# Pic-Kit.net
KiCad netlist of a schematic drawn in Altium Designer
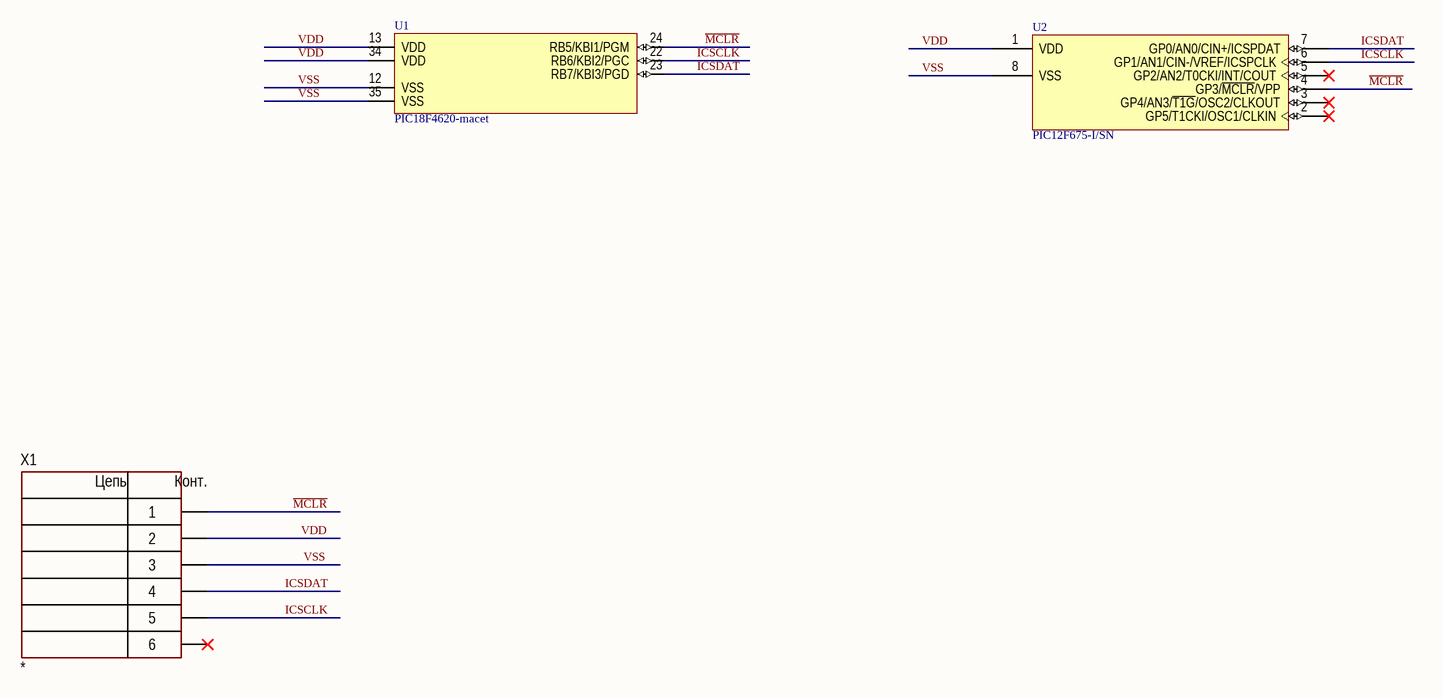
[diagram p0: Pic-Kit.SchDoc]

(export (version "E")
  (design (tool "Eeschema 10.0.6"))
  (components
    (comp (ref "U1")
      (value "PIC18F4620-macet")
      (footprint "PDIP600-P44")
      (description "44-Pin PDIP")
      (libsource (lib "Digital") (part "PIC18F4620-macet"))
    )
    (comp (ref "U2")
      (value "PIC12F675-I/SN")
      (footprint "PDIP300-P8")
      (description "FLASH-Based 8-Bit CMOS Microcontroller, 10-Bit A/D, 8-Pin SOIC 150mil, Industrial Temperature")
      (libsource (lib "Digital") (part "PIC12F675-I/SN"))
    )
    (comp (ref "X1") (value "*") (footprint "CON: PAD 6") (libsource (lib "Connectors") (part "6-Connector")))
  )
  (nets
    (net (code "1") (name "/ICSCLK") (class "Default")
      (node (ref "U1") (pin "22") (pinfunction "RB6/KBI2/PGC_22") (pintype "bidirectional"))
      (node (ref "U2") (pin "6") (pinfunction "GP1/AN1/CIN-/VREF/ICSPCLK_6") (pintype "bidirectional"))
      (node (ref "X1") (pin "5") (pinfunction "5_5") (pintype "power_in"))
    )
    (net (code "2") (name "/ICSDAT") (class "Default")
      (node (ref "U1") (pin "23") (pinfunction "RB7/KBI3/PGD_23") (pintype "bidirectional"))
      (node (ref "U2") (pin "7") (pinfunction "GP0/AN0/CIN+/ICSPDAT_7") (pintype "bidirectional"))
      (node (ref "X1") (pin "4") (pinfunction "4_4") (pintype "power_in"))
    )
    (net (code "3") (name "/VDD") (class "Default")
      (node (ref "U1") (pin "13") (pinfunction "VDD_13") (pintype "power_in"))
      (node (ref "U1") (pin "34") (pinfunction "VDD_34") (pintype "power_in"))
      (node (ref "U2") (pin "1") (pinfunction "VDD_1") (pintype "power_in"))
      (node (ref "X1") (pin "2") (pinfunction "2_2") (pintype "passive"))
    )
    (net (code "4") (name "/VSS") (class "Default")
      (node (ref "U1") (pin "12") (pinfunction "VSS_12") (pintype "power_in"))
      (node (ref "U1") (pin "35") (pinfunction "VSS_35") (pintype "power_in"))
      (node (ref "U2") (pin "8") (pinfunction "VSS_8") (pintype "power_in"))
      (node (ref "X1") (pin "3") (pinfunction "3_3") (pintype "power_in"))
    )
    (net (code "5") (name "/~{MCLR}") (class "Default")
      (node (ref "U1") (pin "24") (pinfunction "RB5/KBI1/PGM_24") (pintype "bidirectional"))
      (node (ref "U2") (pin "4") (pinfunction "GP3/~{MCLR}/VPP_4") (pintype "bidirectional"))
      (node (ref "X1") (pin "1") (pinfunction "1_1") (pintype "passive"))
    )
    (net (code "6") (name "unconnected-(U2-GP2{slash}AN2{slash}T0CKI{slash}INT{slash}COUT-Pad5)") (class "Default")
      (node (ref "U2") (pin "5") (pinfunction "GP2/AN2/T0CKI/INT/COUT_5") (pintype "bidirectional+no_connect"))
    )
    (net (code "7") (name "unconnected-(U2-GP4{slash}AN3{slash}~{T1G}{slash}OSC2{slash}CLKOUT-Pad3)") (class "Default")
      (node (ref "U2") (pin "3") (pinfunction "GP4/AN3/~{T1G}/OSC2/CLKOUT_3") (pintype "bidirectional+no_connect"))
    )
    (net (code "8") (name "unconnected-(U2-GP5{slash}T1CKI{slash}OSC1{slash}CLKIN-Pad2)") (class "Default")
      (node (ref "U2") (pin "2") (pinfunction "GP5/T1CKI/OSC1/CLKIN_2") (pintype "bidirectional+no_connect"))
    )
    (net (code "9") (name "unconnected-(X1-Pad6)") (class "Default")
      (node (ref "X1") (pin "6") (pinfunction "6_6") (pintype "power_in+no_connect"))
    )
  )
)
